# Control.net
KiCad netlist of a schematic drawn in Altium Designer
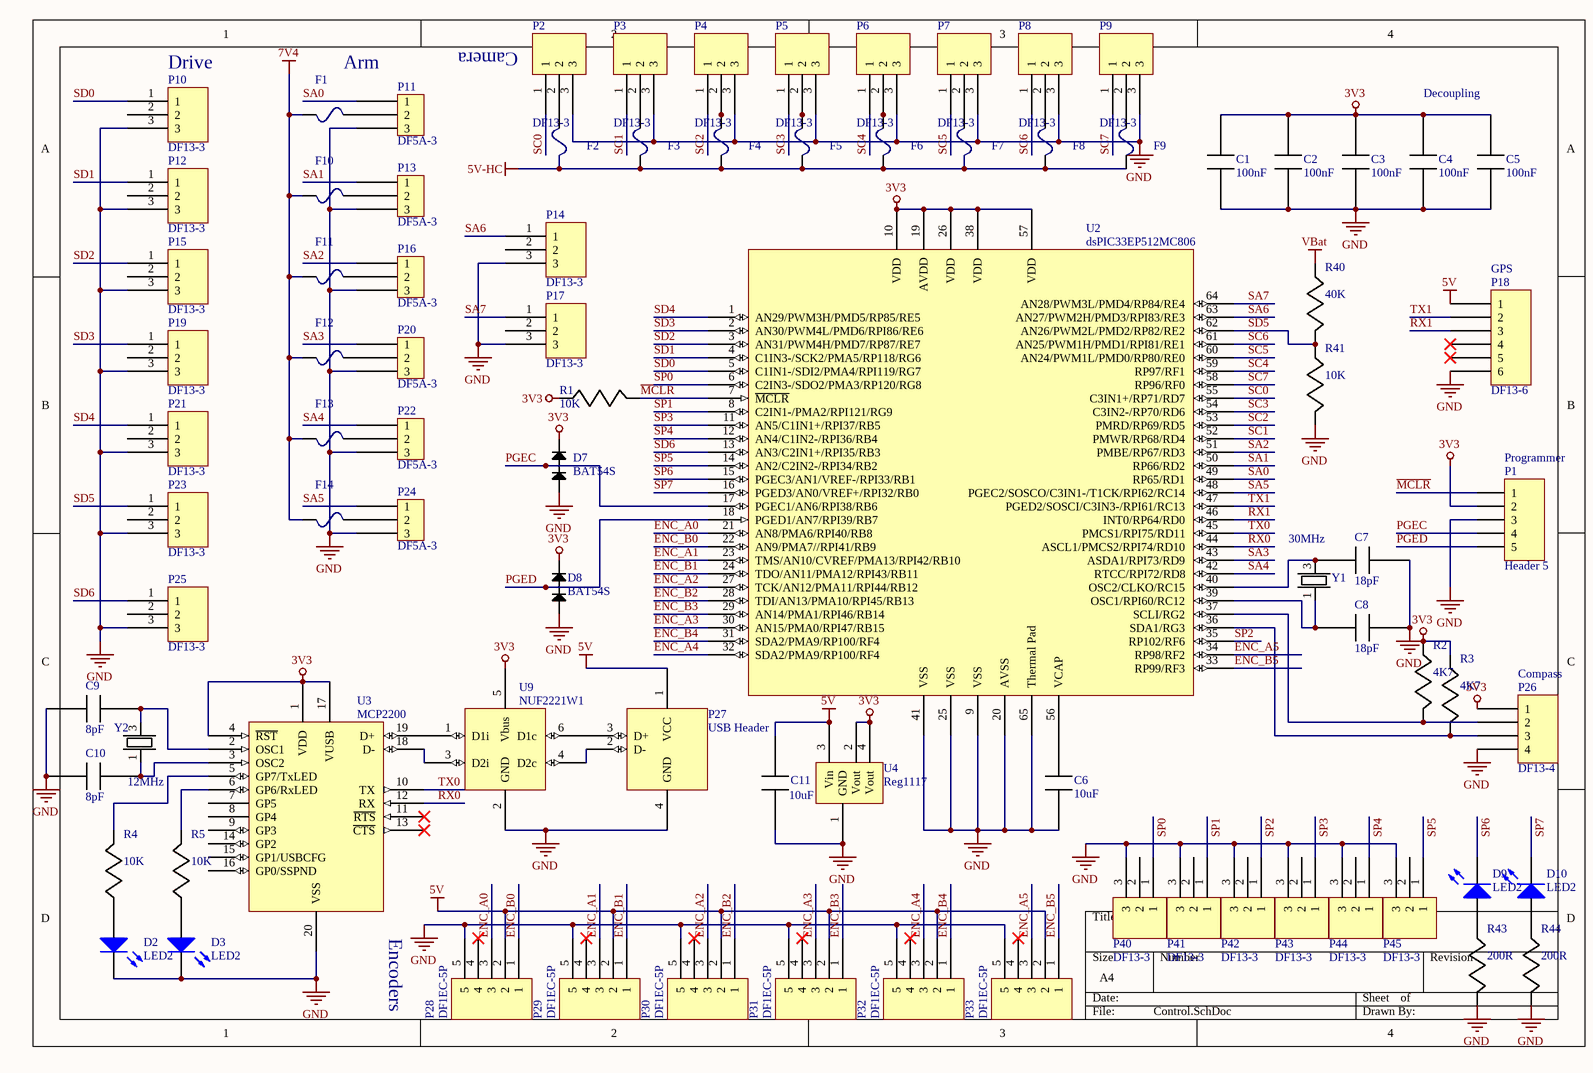
[diagram p0: Control.SchDoc]

(export (version "E")
  (design (tool "Eeschema 10.0.6"))
  (components
    (comp (ref "C1")
      (value "100nF")
      (footprint "1608[0603]")
      (libsource (lib "ControlBoard") (part "Capacitor"))
    )
    (comp (ref "C2")
      (value "100nF")
      (footprint "1608[0603]")
      (libsource (lib "ControlBoard") (part "Capacitor"))
    )
    (comp (ref "C3")
      (value "100nF")
      (footprint "1608[0603]")
      (libsource (lib "ControlBoard") (part "Capacitor"))
    )
    (comp (ref "C4")
      (value "100nF")
      (footprint "1608[0603]")
      (libsource (lib "ControlBoard") (part "Capacitor"))
    )
    (comp (ref "C5")
      (value "100nF")
      (footprint "1608[0603]")
      (libsource (lib "ControlBoard") (part "Capacitor"))
    )
    (comp (ref "C6")
      (value "10uF")
      (footprint "1608[0603]")
      (libsource (lib "ControlBoard") (part "Capacitor"))
    )
    (comp (ref "C7")
      (value "18pF")
      (footprint "1608[0603]")
      (libsource (lib "ControlBoard") (part "Capacitor"))
    )
    (comp (ref "C8")
      (value "18pF")
      (footprint "1608[0603]")
      (libsource (lib "ControlBoard") (part "Capacitor"))
    )
    (comp (ref "C9")
      (value "8pF")
      (footprint "1608[0603]")
      (libsource (lib "ControlBoard") (part "Capacitor"))
    )
    (comp (ref "C10")
      (value "8pF")
      (footprint "1608[0603]")
      (libsource (lib "ControlBoard") (part "Capacitor"))
    )
    (comp (ref "C11")
      (value "~")
      (footprint "1608[0603]")
      (fields (field (name "SIZE") "10uF"))
      (libsource (lib "ControlBoard") (part "Capacitor"))
    )
    (comp (ref "D2")
      (value "LED2")
      (footprint "3.2X1.6X1.1")
      (description "Typical RED, GREEN, YELLOW, AMBER GaAs LED")
      (fields (field (name "PUBLISHER") "Altium Limited"))
      (libsource (lib "Miscellaneous Devices") (part "LED2"))
    )
    (comp (ref "D3")
      (value "LED2")
      (footprint "3.2X1.6X1.1")
      (description "Typical RED, GREEN, YELLOW, AMBER GaAs LED")
      (fields (field (name "PUBLISHER") "Altium Limited"))
      (libsource (lib "Miscellaneous Devices") (part "LED2"))
    )
    (comp (ref "D7")
      (value "BAT54S")
      (footprint "SOT90P240X110-3N")
      (libsource (lib "ControlBoard") (part "BAT54S"))
    )
    (comp (ref "D8")
      (value "BAT54S")
      (footprint "SOT90P240X110-3N")
      (libsource (lib "ControlBoard") (part "BAT54S"))
    )
    (comp (ref "D9")
      (value "LED2")
      (footprint "1608[0603]")
      (description "Typical RED, GREEN, YELLOW, AMBER GaAs LED")
      (fields (field (name "PUBLISHER") "Altium Limited"))
      (libsource (lib "Miscellaneous Devices") (part "LED2"))
    )
    (comp (ref "D10")
      (value "LED2")
      (footprint "1608[0603]")
      (description "Typical RED, GREEN, YELLOW, AMBER GaAs LED")
      (fields (field (name "PUBLISHER") "Altium Limited"))
      (libsource (lib "Miscellaneous Devices") (part "LED2"))
    )
    (comp (ref "F1")
      (value "RSTA 2-BULK")
      (footprint "56400001009")
      (description "FUSE 2A 250/277V RADIAL")
      (libsource (lib "ControlBoard") (part "RSTA 2-BULK"))
    )
    (comp (ref "F2")
      (value "RSTA 2-BULK")
      (footprint "56400001009")
      (description "FUSE 2A 250/277V RADIAL")
      (libsource (lib "ControlBoard") (part "RSTA 2-BULK"))
    )
    (comp (ref "F3")
      (value "RSTA 2-BULK")
      (footprint "56400001009")
      (description "FUSE 2A 250/277V RADIAL")
      (libsource (lib "ControlBoard") (part "RSTA 2-BULK"))
    )
    (comp (ref "F4")
      (value "RSTA 2-BULK")
      (footprint "56400001009")
      (description "FUSE 2A 250/277V RADIAL")
      (libsource (lib "ControlBoard") (part "RSTA 2-BULK"))
    )
    (comp (ref "F5")
      (value "RSTA 2-BULK")
      (footprint "56400001009")
      (description "FUSE 2A 250/277V RADIAL")
      (libsource (lib "ControlBoard") (part "RSTA 2-BULK"))
    )
    (comp (ref "F6")
      (value "RSTA 2-BULK")
      (footprint "56400001009")
      (description "FUSE 2A 250/277V RADIAL")
      (libsource (lib "ControlBoard") (part "RSTA 2-BULK"))
    )
    (comp (ref "F7")
      (value "RSTA 2-BULK")
      (footprint "56400001009")
      (description "FUSE 2A 250/277V RADIAL")
      (libsource (lib "ControlBoard") (part "RSTA 2-BULK"))
    )
    (comp (ref "F8")
      (value "RSTA 2-BULK")
      (footprint "56400001009")
      (description "FUSE 2A 250/277V RADIAL")
      (libsource (lib "ControlBoard") (part "RSTA 2-BULK"))
    )
    (comp (ref "F9")
      (value "RSTA 2-BULK")
      (footprint "56400001009")
      (description "FUSE 2A 250/277V RADIAL")
      (libsource (lib "ControlBoard") (part "RSTA 2-BULK"))
    )
    (comp (ref "F10")
      (value "RSTA 2-BULK")
      (footprint "56400001009")
      (description "FUSE 2A 250/277V RADIAL")
      (libsource (lib "ControlBoard") (part "RSTA 2-BULK"))
    )
    (comp (ref "F11")
      (value "RSTA 2-BULK")
      (footprint "56400001009")
      (description "FUSE 2A 250/277V RADIAL")
      (libsource (lib "ControlBoard") (part "RSTA 2-BULK"))
    )
    (comp (ref "F12")
      (value "RSTA 2-BULK")
      (footprint "56400001009")
      (description "FUSE 2A 250/277V RADIAL")
      (libsource (lib "ControlBoard") (part "RSTA 2-BULK"))
    )
    (comp (ref "F13")
      (value "RSTA 2-BULK")
      (footprint "56400001009")
      (description "FUSE 2A 250/277V RADIAL")
      (libsource (lib "ControlBoard") (part "RSTA 2-BULK"))
    )
    (comp (ref "F14")
      (value "RSTA 2-BULK")
      (footprint "56400001009")
      (description "FUSE 2A 250/277V RADIAL")
      (libsource (lib "ControlBoard") (part "RSTA 2-BULK"))
    )
    (comp (ref "P1")
      (value "Header 5")
      (footprint "HDR1X5")
      (description "Header, 5-Pin")
      (fields (field (name "PUBLISHER") "Altium Limited"))
      (libsource (lib "Miscellaneous Connectors") (part "Header 5"))
    )
    (comp (ref "P2") (value "DF13-3") (footprint "DF13-3") (libsource (lib "") (part "DF13-3_1")))
    (comp (ref "P3") (value "DF13-3") (footprint "DF13-3") (libsource (lib "") (part "DF13-3_1")))
    (comp (ref "P4") (value "DF13-3") (footprint "DF13-3") (libsource (lib "") (part "DF13-3_1")))
    (comp (ref "P5") (value "DF13-3") (footprint "DF13-3") (libsource (lib "") (part "DF13-3_1")))
    (comp (ref "P6") (value "DF13-3") (footprint "DF13-3") (libsource (lib "") (part "DF13-3_1")))
    (comp (ref "P7") (value "DF13-3") (footprint "DF13-3") (libsource (lib "") (part "DF13-3_1")))
    (comp (ref "P8") (value "DF13-3") (footprint "DF13-3") (libsource (lib "") (part "DF13-3_1")))
    (comp (ref "P9") (value "DF13-3") (footprint "DF13-3") (libsource (lib "") (part "DF13-3_1")))
    (comp (ref "P10") (value "DF13-3") (footprint "DF13-3") (libsource (lib "") (part "DF13-3_2")))
    (comp (ref "P11") (value "DF5A-3") (footprint "DF5A-3") (libsource (lib "ControlBoard") (part "DF5A-3")))
    (comp (ref "P12") (value "DF13-3") (footprint "DF13-3") (libsource (lib "") (part "DF13-3_2")))
    (comp (ref "P13") (value "DF5A-3") (footprint "DF5A-3") (libsource (lib "ControlBoard") (part "DF5A-3")))
    (comp (ref "P14") (value "DF13-3") (footprint "DF13-3") (libsource (lib "") (part "DF13-3_2")))
    (comp (ref "P15") (value "DF13-3") (footprint "DF13-3") (libsource (lib "") (part "DF13-3_2")))
    (comp (ref "P16") (value "DF5A-3") (footprint "DF5A-3") (libsource (lib "ControlBoard") (part "DF5A-3")))
    (comp (ref "P17") (value "DF13-3") (footprint "DF13-3") (libsource (lib "") (part "DF13-3_2")))
    (comp (ref "P18")
      (value "DF13-6")
      (footprint "DF13-6S-1.25H")
      (libsource (lib "ControlBoard") (part "DF13-6"))
    )
    (comp (ref "P19") (value "DF13-3") (footprint "DF13-3") (libsource (lib "") (part "DF13-3_2")))
    (comp (ref "P20") (value "DF5A-3") (footprint "DF5A-3") (libsource (lib "ControlBoard") (part "DF5A-3")))
    (comp (ref "P21") (value "DF13-3") (footprint "DF13-3") (libsource (lib "") (part "DF13-3_2")))
    (comp (ref "P22") (value "DF5A-3") (footprint "DF5A-3") (libsource (lib "ControlBoard") (part "DF5A-3")))
    (comp (ref "P23") (value "DF13-3") (footprint "DF13-3") (libsource (lib "") (part "DF13-3_2")))
    (comp (ref "P24") (value "DF5A-3") (footprint "DF5A-3") (libsource (lib "ControlBoard") (part "DF5A-3")))
    (comp (ref "P25") (value "DF13-3") (footprint "DF13-3") (libsource (lib "") (part "DF13-3_2")))
    (comp (ref "P26")
      (value "DF13-4")
      (footprint "DF13-4S-1.25H")
      (libsource (lib "ControlBoard") (part "DF13-4"))
    )
    (comp (ref "P27")
      (value "USB Header")
      (footprint "USB-B")
      (libsource (lib "ControlBoard") (part "USB Header"))
    )
    (comp (ref "P28")
      (value "DF1EC-5P")
      (footprint "DF1EC-4P")
      (libsource (lib "ControlBoard") (part "DF1EC-5P"))
    )
    (comp (ref "P29")
      (value "DF1EC-5P")
      (footprint "DF1EC-4P")
      (libsource (lib "ControlBoard") (part "DF1EC-5P"))
    )
    (comp (ref "P30")
      (value "DF1EC-5P")
      (footprint "DF1EC-4P")
      (libsource (lib "ControlBoard") (part "DF1EC-5P"))
    )
    (comp (ref "P31")
      (value "DF1EC-5P")
      (footprint "DF1EC-4P")
      (libsource (lib "ControlBoard") (part "DF1EC-5P"))
    )
    (comp (ref "P32")
      (value "DF1EC-5P")
      (footprint "DF1EC-4P")
      (libsource (lib "ControlBoard") (part "DF1EC-5P"))
    )
    (comp (ref "P33")
      (value "DF1EC-5P")
      (footprint "DF1EC-4P")
      (libsource (lib "ControlBoard") (part "DF1EC-5P"))
    )
    (comp (ref "P40") (value "DF13-3") (footprint "DF13-3") (libsource (lib "ControlBoard") (part "DF13-3")))
    (comp (ref "P41") (value "DF13-3") (footprint "DF13-3") (libsource (lib "ControlBoard") (part "DF13-3")))
    (comp (ref "P42") (value "DF13-3") (footprint "DF13-3") (libsource (lib "ControlBoard") (part "DF13-3")))
    (comp (ref "P43") (value "DF13-3") (footprint "DF13-3") (libsource (lib "ControlBoard") (part "DF13-3")))
    (comp (ref "P44") (value "DF13-3") (footprint "DF13-3") (libsource (lib "ControlBoard") (part "DF13-3")))
    (comp (ref "P45") (value "DF13-3") (footprint "DF13-3") (libsource (lib "ControlBoard") (part "DF13-3")))
    (comp (ref "R1")
      (value "~")
      (footprint "1608[0603]")
      (fields (field (name "SIZE") "10K"))
      (libsource (lib "ControlBoard") (part "Resistor"))
    )
    (comp (ref "R2")
      (value "~")
      (footprint "1608[0603]")
      (fields (field (name "SIZE") "4K7"))
      (libsource (lib "ControlBoard") (part "Resistor"))
    )
    (comp (ref "R3")
      (value "~")
      (footprint "1608[0603]")
      (fields (field (name "SIZE") "4K7"))
      (libsource (lib "ControlBoard") (part "Resistor"))
    )
    (comp (ref "R4")
      (value "~")
      (footprint "1608[0603]")
      (fields (field (name "SIZE") "10K"))
      (libsource (lib "ControlBoard") (part "Resistor"))
    )
    (comp (ref "R5")
      (value "~")
      (footprint "1608[0603]")
      (fields (field (name "SIZE") "10K"))
      (libsource (lib "ControlBoard") (part "Resistor"))
    )
    (comp (ref "R40")
      (value "~")
      (footprint "1608[0603]")
      (fields (field (name "SIZE") "40K"))
      (libsource (lib "ControlBoard") (part "Resistor"))
    )
    (comp (ref "R41")
      (value "~")
      (footprint "1608[0603]")
      (fields (field (name "SIZE") "10K"))
      (libsource (lib "ControlBoard") (part "Resistor"))
    )
    (comp (ref "R43")
      (value "~")
      (footprint "1608[0603]")
      (fields (field (name "SIZE") "200R"))
      (libsource (lib "ControlBoard") (part "Resistor"))
    )
    (comp (ref "R44")
      (value "~")
      (footprint "1608[0603]")
      (fields (field (name "SIZE") "200R"))
      (libsource (lib "ControlBoard") (part "Resistor"))
    )
    (comp (ref "U2")
      (value "dsPIC33EP512MC806")
      (footprint "QFN50P900X900X100_HS-65N")
      (libsource (lib "ControlBoard") (part "dsPIC33EP512MC806"))
    )
    (comp (ref "U3")
      (value "MCP2200")
      (footprint "SOP65P780X200-20N")
      (libsource (lib "ControlBoard") (part "MCP2200"))
    )
    (comp (ref "U4")
      (value "Reg1117")
      (footprint "SOT230P700X180-4N")
      (libsource (lib "ControlBoard") (part "Reg1117"))
    )
    (comp (ref "U9")
      (value "NUF2221W1")
      (footprint "TSOP65P210X110-6N")
      (libsource (lib "ControlBoard") (part "NUF2221W1"))
    )
    (comp (ref "Y1")
      (value "30MHz")
      (footprint "7M-30.000MBBK-T")
      (fields (field (name "Comment") "NX5032GC"))
      (libsource (lib "ControlBoard") (part "NX5032GC"))
    )
    (comp (ref "Y2")
      (value "12MHz")
      (footprint "NX5032GC")
      (fields (field (name "Comment") "NX5032GC"))
      (libsource (lib "ControlBoard") (part "NX5032GC"))
    )
  )
  (nets
    (net (code "1") (name "/ENC_A0") (class "Default")
      (node (ref "P28") (pin "3") (pinfunction "3_3") (pintype "passive"))
      (node (ref "U2") (pin "21") (pinfunction "AN8/PMA6/RPI40/RB8_21") (pintype "bidirectional"))
    )
    (net (code "2") (name "/ENC_A1") (class "Default")
      (node (ref "P29") (pin "3") (pinfunction "3_3") (pintype "passive"))
      (node (ref "U2") (pin "23") (pinfunction "TMS/AN10/CVREF/PMA13/RPI42/RB10_23") (pintype "bidirectional"))
    )
    (net (code "3") (name "/ENC_A2") (class "Default")
      (node (ref "P30") (pin "3") (pinfunction "3_3") (pintype "passive"))
      (node (ref "U2") (pin "27") (pinfunction "TCK/AN12/PMA11/RPI44/RB12_27") (pintype "bidirectional"))
    )
    (net (code "4") (name "/ENC_A3") (class "Default")
      (node (ref "P31") (pin "3") (pinfunction "3_3") (pintype "passive"))
      (node (ref "U2") (pin "30") (pinfunction "AN15/PMA0/RPI47/RB15_30") (pintype "bidirectional"))
    )
    (net (code "5") (name "/ENC_A4") (class "Default")
      (node (ref "P32") (pin "3") (pinfunction "3_3") (pintype "passive"))
      (node (ref "U2") (pin "32") (pinfunction "SDA2/PMA9/RP100/RF4_32") (pintype "bidirectional"))
    )
    (net (code "6") (name "/ENC_A5") (class "Default")
      (node (ref "P33") (pin "3") (pinfunction "3_3") (pintype "passive"))
      (node (ref "U2") (pin "34") (pinfunction "RP98/RF2_34") (pintype "bidirectional"))
    )
    (net (code "7") (name "/ENC_B0") (class "Default")
      (node (ref "P28") (pin "1") (pinfunction "1_1") (pintype "passive"))
      (node (ref "U2") (pin "22") (pinfunction "AN9/PMA7//RPI41/RB9_22") (pintype "bidirectional"))
    )
    (net (code "8") (name "/ENC_B1") (class "Default")
      (node (ref "P29") (pin "1") (pinfunction "1_1") (pintype "passive"))
      (node (ref "U2") (pin "24") (pinfunction "TDO/AN11/PMA12/RPI43/RB11_24") (pintype "bidirectional"))
    )
    (net (code "9") (name "/ENC_B2") (class "Default")
      (node (ref "P30") (pin "1") (pinfunction "1_1") (pintype "passive"))
      (node (ref "U2") (pin "28") (pinfunction "TDI/AN13/PMA10/RPI45/RB13_28") (pintype "bidirectional"))
    )
    (net (code "10") (name "/ENC_B3") (class "Default")
      (node (ref "P31") (pin "1") (pinfunction "1_1") (pintype "passive"))
      (node (ref "U2") (pin "29") (pinfunction "AN14/PMA1/RPI46/RB14_29") (pintype "bidirectional"))
    )
    (net (code "11") (name "/ENC_B4") (class "Default")
      (node (ref "P32") (pin "1") (pinfunction "1_1") (pintype "passive"))
      (node (ref "U2") (pin "31") (pinfunction "SDA2/PMA9/RP100/RF4_31") (pintype "bidirectional"))
    )
    (net (code "12") (name "/ENC_B5") (class "Default")
      (node (ref "P33") (pin "1") (pinfunction "1_1") (pintype "passive"))
      (node (ref "U2") (pin "33") (pinfunction "RP99/RF3_33") (pintype "bidirectional"))
    )
    (net (code "13") (name "/PGEC") (class "Default")
      (node (ref "D7") (pin "3") (pinfunction "D1i_3") (pintype "passive"))
      (node (ref "P1") (pin "4") (pinfunction "4_4") (pintype "passive"))
      (node (ref "U2") (pin "17") (pinfunction "PGEC1/AN6/RPI38/RB6_17") (pintype "bidirectional"))
    )
    (net (code "14") (name "/PGED") (class "Default")
      (node (ref "D8") (pin "3") (pinfunction "D1i_3") (pintype "passive"))
      (node (ref "P1") (pin "5") (pinfunction "5_5") (pintype "passive"))
      (node (ref "U2") (pin "18") (pinfunction "PGED1/AN7/RPI39/RB7_18") (pintype "input"))
    )
    (net (code "15") (name "/RX0") (class "Default")
      (node (ref "U2") (pin "44") (pinfunction "ASCL1/PMCS2/RPI74/RD10_44") (pintype "bidirectional"))
      (node (ref "U3") (pin "12") (pinfunction "RX_12") (pintype "input"))
    )
    (net (code "16") (name "/RX1") (class "Default")
      (node (ref "P18") (pin "3") (pinfunction "3_3") (pintype "passive"))
      (node (ref "U2") (pin "46") (pinfunction "INT0/RP64/RD0_46") (pintype "bidirectional"))
    )
    (net (code "17") (name "/SA0") (class "Default")
      (node (ref "P11") (pin "1") (pinfunction "1_1") (pintype "passive"))
      (node (ref "U2") (pin "49") (pinfunction "RP65/RD1_49") (pintype "bidirectional"))
    )
    (net (code "18") (name "/SA1") (class "Default")
      (node (ref "P13") (pin "1") (pinfunction "1_1") (pintype "passive"))
      (node (ref "U2") (pin "50") (pinfunction "RP66/RD2_50") (pintype "bidirectional"))
    )
    (net (code "19") (name "/SA2") (class "Default")
      (node (ref "P16") (pin "1") (pinfunction "1_1") (pintype "passive"))
      (node (ref "U2") (pin "51") (pinfunction "PMBE/RP67/RD3_51") (pintype "bidirectional"))
    )
    (net (code "20") (name "/SA3") (class "Default")
      (node (ref "P20") (pin "1") (pinfunction "1_1") (pintype "passive"))
      (node (ref "U2") (pin "43") (pinfunction "ASDA1/RPI73/RD9_43") (pintype "bidirectional"))
    )
    (net (code "21") (name "/SA4") (class "Default")
      (node (ref "P22") (pin "1") (pinfunction "1_1") (pintype "passive"))
      (node (ref "U2") (pin "42") (pinfunction "RTCC/RPI72/RD8_42") (pintype "bidirectional"))
    )
    (net (code "22") (name "/SA5") (class "Default")
      (node (ref "P24") (pin "1") (pinfunction "1_1") (pintype "passive"))
      (node (ref "U2") (pin "48") (pinfunction "PGEC2/SOSCO/C3IN1-/T1CK/RPI62/RC14_48") (pintype "bidirectional"))
    )
    (net (code "23") (name "/SA6") (class "Default")
      (node (ref "P14") (pin "1") (pinfunction "1_1") (pintype "passive"))
      (node (ref "U2") (pin "63") (pinfunction "AN27/PWM2H/PMD3/RPI83/RE3_63") (pintype "bidirectional"))
    )
    (net (code "24") (name "/SA7") (class "Default")
      (node (ref "P17") (pin "1") (pinfunction "1_1") (pintype "passive"))
      (node (ref "U2") (pin "64") (pinfunction "AN28/PWM3L/PMD4/RP84/RE4_64") (pintype "bidirectional"))
    )
    (net (code "25") (name "/SC0") (class "Default")
      (node (ref "P2") (pin "1") (pinfunction "1_1") (pintype "passive"))
      (node (ref "U2") (pin "55") (pinfunction "C3IN1+/RP71/RD7_55") (pintype "bidirectional"))
    )
    (net (code "26") (name "/SC1") (class "Default")
      (node (ref "P3") (pin "1") (pinfunction "1_1") (pintype "passive"))
      (node (ref "U2") (pin "52") (pinfunction "PMWR/RP68/RD4_52") (pintype "bidirectional"))
    )
    (net (code "27") (name "/SC2") (class "Default")
      (node (ref "P4") (pin "1") (pinfunction "1_1") (pintype "passive"))
      (node (ref "U2") (pin "53") (pinfunction "PMRD/RP69/RD5_53") (pintype "bidirectional"))
    )
    (net (code "28") (name "/SC3") (class "Default")
      (node (ref "P5") (pin "1") (pinfunction "1_1") (pintype "passive"))
      (node (ref "U2") (pin "54") (pinfunction "C3IN2-/RP70/RD6_54") (pintype "bidirectional"))
    )
    (net (code "29") (name "/SC4") (class "Default")
      (node (ref "P6") (pin "1") (pinfunction "1_1") (pintype "passive"))
      (node (ref "U2") (pin "59") (pinfunction "RP97/RF1_59") (pintype "bidirectional"))
    )
    (net (code "30") (name "/SC5") (class "Default")
      (node (ref "P7") (pin "1") (pinfunction "1_1") (pintype "passive"))
      (node (ref "U2") (pin "60") (pinfunction "AN24/PWM1L/PMD0/RP80/RE0_60") (pintype "bidirectional"))
    )
    (net (code "31") (name "/SC6") (class "Default")
      (node (ref "P8") (pin "1") (pinfunction "1_1") (pintype "passive"))
      (node (ref "U2") (pin "61") (pinfunction "AN25/PWM1H/PMD1/RPI81/RE1_61") (pintype "bidirectional"))
    )
    (net (code "32") (name "/SC7") (class "Default")
      (node (ref "P9") (pin "1") (pinfunction "1_1") (pintype "passive"))
      (node (ref "U2") (pin "58") (pinfunction "RP96/RF0_58") (pintype "bidirectional"))
    )
    (net (code "33") (name "/SD0") (class "Default")
      (node (ref "P10") (pin "1") (pinfunction "1_1") (pintype "passive"))
      (node (ref "U2") (pin "5") (pinfunction "C1IN1-/SDI2/PMA4/RPI119/RG7_5") (pintype "bidirectional"))
    )
    (net (code "34") (name "/SD1") (class "Default")
      (node (ref "P12") (pin "1") (pinfunction "1_1") (pintype "passive"))
      (node (ref "U2") (pin "4") (pinfunction "C1IN3-/SCK2/PMA5/RP118/RG6_4") (pintype "bidirectional"))
    )
    (net (code "35") (name "/SD2") (class "Default")
      (node (ref "P15") (pin "1") (pinfunction "1_1") (pintype "passive"))
      (node (ref "U2") (pin "3") (pinfunction "AN31/PWM4H/PMD7/RP87/RE7_3") (pintype "bidirectional"))
    )
    (net (code "36") (name "/SD3") (class "Default")
      (node (ref "P19") (pin "1") (pinfunction "1_1") (pintype "passive"))
      (node (ref "U2") (pin "2") (pinfunction "AN30/PWM4L/PMD6/RPI86/RE6_2") (pintype "bidirectional"))
    )
    (net (code "37") (name "/SD4") (class "Default")
      (node (ref "P21") (pin "1") (pinfunction "1_1") (pintype "passive"))
      (node (ref "U2") (pin "1") (pinfunction "AN29/PWM3H/PMD5/RP85/RE5_1") (pintype "bidirectional"))
    )
    (net (code "38") (name "/SD5") (class "Default")
      (node (ref "P23") (pin "1") (pinfunction "1_1") (pintype "passive"))
      (node (ref "R40") (pin "1") (pinfunction "1_1") (pintype "passive"))
      (node (ref "R41") (pin "2") (pinfunction "2_2") (pintype "passive"))
      (node (ref "U2") (pin "62") (pinfunction "AN26/PWM2L/PMD2/RP82/RE2_62") (pintype "bidirectional"))
    )
    (net (code "39") (name "/SD6") (class "Default")
      (node (ref "P25") (pin "1") (pinfunction "1_1") (pintype "passive"))
      (node (ref "U2") (pin "13") (pinfunction "AN3/C2IN1+/RPI35/RB3_13") (pintype "bidirectional"))
    )
    (net (code "40") (name "/SP0") (class "Default")
      (node (ref "P40") (pin "1") (pinfunction "1_1") (pintype "passive"))
      (node (ref "U2") (pin "6") (pinfunction "C2IN3-/SDO2/PMA3/RP120/RG8_6") (pintype "bidirectional"))
    )
    (net (code "41") (name "/SP1") (class "Default")
      (node (ref "P41") (pin "1") (pinfunction "1_1") (pintype "passive"))
      (node (ref "U2") (pin "8") (pinfunction "C2IN1-/PMA2/RPI121/RG9_8") (pintype "bidirectional"))
    )
    (net (code "42") (name "/SP2") (class "Default")
      (node (ref "P42") (pin "1") (pinfunction "1_1") (pintype "passive"))
      (node (ref "U2") (pin "35") (pinfunction "RP102/RF6_35") (pintype "bidirectional"))
    )
    (net (code "43") (name "/SP3") (class "Default")
      (node (ref "P43") (pin "1") (pinfunction "1_1") (pintype "passive"))
      (node (ref "U2") (pin "11") (pinfunction "AN5/C1IN1+/RPI37/RB5_11") (pintype "bidirectional"))
    )
    (net (code "44") (name "/SP4") (class "Default")
      (node (ref "P44") (pin "1") (pinfunction "1_1") (pintype "passive"))
      (node (ref "U2") (pin "12") (pinfunction "AN4/C1IN2-/RPI36/RB4_12") (pintype "bidirectional"))
    )
    (net (code "45") (name "/SP5") (class "Default")
      (node (ref "P45") (pin "1") (pinfunction "1_1") (pintype "passive"))
      (node (ref "U2") (pin "14") (pinfunction "AN2/C2IN2-/RPI34/RB2_14") (pintype "bidirectional"))
    )
    (net (code "46") (name "/SP6") (class "Default")
      (node (ref "D9") (pin "2") (pinfunction "K_2") (pintype "passive"))
      (node (ref "U2") (pin "15") (pinfunction "PGEC3/AN1/VREF-/RPI33/RB1_15") (pintype "bidirectional"))
    )
    (net (code "47") (name "/SP7") (class "Default")
      (node (ref "D10") (pin "2") (pinfunction "K_2") (pintype "passive"))
      (node (ref "U2") (pin "16") (pinfunction "PGED3/AN0/VREF+/RPI32/RB0_16") (pintype "bidirectional"))
    )
    (net (code "48") (name "/TX0") (class "Default")
      (node (ref "U2") (pin "45") (pinfunction "PMCS1/RPI75/RD11_45") (pintype "bidirectional"))
      (node (ref "U3") (pin "10") (pinfunction "TX_10") (pintype "output"))
    )
    (net (code "49") (name "/TX1") (class "Default")
      (node (ref "P18") (pin "2") (pinfunction "2_2") (pintype "passive"))
      (node (ref "U2") (pin "47") (pinfunction "PGED2/SOSCI/C3IN3-/RPI61/RC13_47") (pintype "bidirectional"))
    )
    (net (code "50") (name "/~{MCLR}") (class "Default")
      (node (ref "P1") (pin "1") (pinfunction "1_1") (pintype "passive"))
      (node (ref "R1") (pin "1") (pinfunction "1_1") (pintype "passive"))
      (node (ref "U2") (pin "7") (pinfunction "~{MCLR}_7") (pintype "input"))
    )
    (net (code "51") (name "3V3") (class "Default")
      (node (ref "C1") (pin "2") (pinfunction "2_2") (pintype "passive"))
      (node (ref "C2") (pin "2") (pinfunction "2_2") (pintype "passive"))
      (node (ref "C3") (pin "2") (pinfunction "2_2") (pintype "passive"))
      (node (ref "C4") (pin "2") (pinfunction "2_2") (pintype "passive"))
      (node (ref "C5") (pin "2") (pinfunction "2_2") (pintype "passive"))
      (node (ref "D7") (pin "2") (pinfunction "D1i_2") (pintype "passive"))
      (node (ref "D8") (pin "2") (pinfunction "D1i_2") (pintype "passive"))
      (node (ref "P1") (pin "2") (pinfunction "2_2") (pintype "passive"))
      (node (ref "P26") (pin "1") (pinfunction "1_1") (pintype "passive"))
      (node (ref "R1") (pin "2") (pinfunction "2_2") (pintype "passive"))
      (node (ref "R2") (pin "2") (pinfunction "2_2") (pintype "passive"))
      (node (ref "R3") (pin "2") (pinfunction "2_2") (pintype "passive"))
      (node (ref "U2") (pin "10") (pinfunction "VDD_10") (pintype "power_in"))
      (node (ref "U2") (pin "19") (pinfunction "AVDD_19") (pintype "power_in"))
      (node (ref "U2") (pin "26") (pinfunction "VDD_26") (pintype "passive"))
      (node (ref "U2") (pin "38") (pinfunction "VDD_38") (pintype "power_in"))
      (node (ref "U2") (pin "57") (pinfunction "VDD_57") (pintype "power_in"))
      (node (ref "U3") (pin "1") (pinfunction "VDD_1") (pintype "passive"))
      (node (ref "U3") (pin "17") (pinfunction "VUSB_17") (pintype "power_in"))
      (node (ref "U3") (pin "4") (pinfunction "~{RST}_4") (pintype "input"))
      (node (ref "U4") (pin "2") (pinfunction "Vout_2") (pintype "power_in"))
      (node (ref "U4") (pin "4") (pinfunction "Vout_4") (pintype "power_in"))
      (node (ref "U9") (pin "5") (pinfunction "Vbus_5") (pintype "power_in"))
    )
    (net (code "52") (name "5V") (class "Default")
      (node (ref "C11") (pin "2") (pinfunction "2_2") (pintype "passive"))
      (node (ref "P18") (pin "1") (pinfunction "1_1") (pintype "passive"))
      (node (ref "P27") (pin "1") (pinfunction "VCC_1") (pintype "power_in"))
      (node (ref "P28") (pin "2") (pinfunction "2_2") (pintype "passive"))
      (node (ref "P29") (pin "2") (pinfunction "2_2") (pintype "passive"))
      (node (ref "P30") (pin "2") (pinfunction "2_2") (pintype "passive"))
      (node (ref "P31") (pin "2") (pinfunction "2_2") (pintype "passive"))
      (node (ref "P32") (pin "2") (pinfunction "2_2") (pintype "passive"))
      (node (ref "P33") (pin "2") (pinfunction "2_2") (pintype "passive"))
      (node (ref "U4") (pin "3") (pinfunction "Vin_3") (pintype "power_in"))
    )
    (net (code "53") (name "5V-HC") (class "Default")
      (node (ref "F2") (pin "2") (pinfunction "31_2") (pintype "passive"))
      (node (ref "F3") (pin "1") (pinfunction "30_1") (pintype "passive"))
      (node (ref "F4") (pin "1") (pinfunction "30_1") (pintype "passive"))
      (node (ref "F5") (pin "1") (pinfunction "30_1") (pintype "passive"))
      (node (ref "F6") (pin "1") (pinfunction "30_1") (pintype "passive"))
      (node (ref "F7") (pin "1") (pinfunction "30_1") (pintype "passive"))
      (node (ref "F8") (pin "1") (pinfunction "30_1") (pintype "passive"))
      (node (ref "F9") (pin "1") (pinfunction "30_1") (pintype "passive"))
    )
    (net (code "54") (name "7V4") (class "Default")
      (node (ref "F1") (pin "1") (pinfunction "30_1") (pintype "passive"))
      (node (ref "F10") (pin "1") (pinfunction "30_1") (pintype "passive"))
      (node (ref "F11") (pin "1") (pinfunction "30_1") (pintype "passive"))
      (node (ref "F12") (pin "1") (pinfunction "30_1") (pintype "passive"))
      (node (ref "F13") (pin "1") (pinfunction "30_1") (pintype "passive"))
      (node (ref "F14") (pin "1") (pinfunction "30_1") (pintype "passive"))
    )
    (net (code "55") (name "GND") (class "Default")
      (node (ref "C1") (pin "1") (pinfunction "1_1") (pintype "passive"))
      (node (ref "C10") (pin "2") (pinfunction "2_2") (pintype "passive"))
      (node (ref "C11") (pin "1") (pinfunction "1_1") (pintype "passive"))
      (node (ref "C2") (pin "1") (pinfunction "1_1") (pintype "passive"))
      (node (ref "C3") (pin "1") (pinfunction "1_1") (pintype "passive"))
      (node (ref "C4") (pin "1") (pinfunction "1_1") (pintype "passive"))
      (node (ref "C5") (pin "1") (pinfunction "1_1") (pintype "passive"))
      (node (ref "C6") (pin "1") (pinfunction "1_1") (pintype "passive"))
      (node (ref "C7") (pin "1") (pinfunction "1_1") (pintype "passive"))
      (node (ref "C8") (pin "1") (pinfunction "1_1") (pintype "passive"))
      (node (ref "C9") (pin "2") (pinfunction "2_2") (pintype "passive"))
      (node (ref "D2") (pin "2") (pinfunction "K_2") (pintype "passive"))
      (node (ref "D3") (pin "2") (pinfunction "K_2") (pintype "passive"))
      (node (ref "D7") (pin "1") (pinfunction "D1i_1") (pintype "passive"))
      (node (ref "D8") (pin "1") (pinfunction "D1i_1") (pintype "passive"))
      (node (ref "P1") (pin "3") (pinfunction "3_3") (pintype "passive"))
      (node (ref "P10") (pin "3") (pinfunction "3_3") (pintype "passive"))
      (node (ref "P11") (pin "3") (pinfunction "3_3") (pintype "passive"))
      (node (ref "P12") (pin "3") (pinfunction "3_3") (pintype "passive"))
      (node (ref "P13") (pin "3") (pinfunction "3_3") (pintype "passive"))
      (node (ref "P14") (pin "3") (pinfunction "3_3") (pintype "passive"))
      (node (ref "P15") (pin "3") (pinfunction "3_3") (pintype "passive"))
      (node (ref "P16") (pin "3") (pinfunction "3_3") (pintype "passive"))
      (node (ref "P17") (pin "3") (pinfunction "3_3") (pintype "passive"))
      (node (ref "P18") (pin "6") (pinfunction "6_6") (pintype "passive"))
      (node (ref "P19") (pin "3") (pinfunction "3_3") (pintype "passive"))
      (node (ref "P2") (pin "3") (pinfunction "3_3") (pintype "passive"))
      (node (ref "P20") (pin "3") (pinfunction "3_3") (pintype "passive"))
      (node (ref "P21") (pin "3") (pinfunction "3_3") (pintype "passive"))
      (node (ref "P22") (pin "3") (pinfunction "3_3") (pintype "passive"))
      (node (ref "P23") (pin "3") (pinfunction "3_3") (pintype "passive"))
      (node (ref "P24") (pin "3") (pinfunction "3_3") (pintype "passive"))
      (node (ref "P25") (pin "3") (pinfunction "3_3") (pintype "passive"))
      (node (ref "P26") (pin "4") (pinfunction "4_4") (pintype "passive"))
      (node (ref "P27") (pin "4") (pinfunction "GND_4") (pintype "power_in"))
      (node (ref "P28") (pin "5") (pinfunction "5_5") (pintype "passive"))
      (node (ref "P29") (pin "5") (pinfunction "5_5") (pintype "passive"))
      (node (ref "P3") (pin "3") (pinfunction "3_3") (pintype "passive"))
      (node (ref "P30") (pin "5") (pinfunction "5_5") (pintype "passive"))
      (node (ref "P31") (pin "5") (pinfunction "5_5") (pintype "passive"))
      (node (ref "P32") (pin "5") (pinfunction "5_5") (pintype "passive"))
      (node (ref "P33") (pin "5") (pinfunction "5_5") (pintype "passive"))
      (node (ref "P4") (pin "3") (pinfunction "3_3") (pintype "passive"))
      (node (ref "P40") (pin "3") (pinfunction "3_3") (pintype "passive"))
      (node (ref "P41") (pin "3") (pinfunction "3_3") (pintype "passive"))
      (node (ref "P42") (pin "3") (pinfunction "3_3") (pintype "passive"))
      (node (ref "P43") (pin "3") (pinfunction "3_3") (pintype "passive"))
      (node (ref "P44") (pin "3") (pinfunction "3_3") (pintype "passive"))
      (node (ref "P45") (pin "3") (pinfunction "3_3") (pintype "passive"))
      (node (ref "P5") (pin "3") (pinfunction "3_3") (pintype "passive"))
      (node (ref "P6") (pin "3") (pinfunction "3_3") (pintype "passive"))
      (node (ref "P7") (pin "3") (pinfunction "3_3") (pintype "passive"))
      (node (ref "P8") (pin "3") (pinfunction "3_3") (pintype "passive"))
      (node (ref "P9") (pin "3") (pinfunction "3_3") (pintype "passive"))
      (node (ref "R41") (pin "1") (pinfunction "1_1") (pintype "passive"))
      (node (ref "R43") (pin "1") (pinfunction "1_1") (pintype "passive"))
      (node (ref "R44") (pin "1") (pinfunction "1_1") (pintype "passive"))
      (node (ref "U2") (pin "20") (pinfunction "AVSS_20") (pintype "passive"))
      (node (ref "U2") (pin "25") (pinfunction "VSS_25") (pintype "passive"))
      (node (ref "U2") (pin "41") (pinfunction "VSS_41") (pintype "power_in"))
      (node (ref "U2") (pin "65") (pinfunction "Thermal_Pad_65") (pintype "power_in"))
      (node (ref "U2") (pin "9") (pinfunction "VSS_9") (pintype "power_in"))
      (node (ref "U3") (pin "20") (pinfunction "VSS_20") (pintype "power_in"))
      (node (ref "U4") (pin "1") (pinfunction "GND_1") (pintype "power_in"))
      (node (ref "U9") (pin "2") (pinfunction "GND_2") (pintype "passive"))
    )
    (net (code "56") (name "Net-(D2-A)") (class "Default")
      (node (ref "D2") (pin "1") (pinfunction "A_1") (pintype "passive"))
      (node (ref "R4") (pin "2") (pinfunction "2_2") (pintype "passive"))
    )
    (net (code "57") (name "Net-(D3-A)") (class "Default")
      (node (ref "D3") (pin "1") (pinfunction "A_1") (pintype "passive"))
      (node (ref "R5") (pin "2") (pinfunction "2_2") (pintype "passive"))
    )
    (net (code "58") (name "Net-(D9-A)") (class "Default")
      (node (ref "D9") (pin "1") (pinfunction "A_1") (pintype "passive"))
      (node (ref "R43") (pin "2") (pinfunction "2_2") (pintype "passive"))
    )
    (net (code "59") (name "Net-(D10-A)") (class "Default")
      (node (ref "D10") (pin "1") (pinfunction "A_1") (pintype "passive"))
      (node (ref "R44") (pin "2") (pinfunction "2_2") (pintype "passive"))
    )
    (net (code "60") (name "Net-(F1-31)") (class "Default")
      (node (ref "F1") (pin "2") (pinfunction "31_2") (pintype "passive"))
      (node (ref "P11") (pin "2") (pinfunction "2_2") (pintype "passive"))
    )
    (net (code "61") (name "Net-(F2-30)") (class "Default")
      (node (ref "F2") (pin "1") (pinfunction "30_1") (pintype "passive"))
      (node (ref "P2") (pin "2") (pinfunction "2_2") (pintype "passive"))
    )
    (net (code "62") (name "Net-(F3-31)") (class "Default")
      (node (ref "F3") (pin "2") (pinfunction "31_2") (pintype "passive"))
      (node (ref "P3") (pin "2") (pinfunction "2_2") (pintype "passive"))
    )
    (net (code "63") (name "Net-(F4-31)") (class "Default")
      (node (ref "F4") (pin "2") (pinfunction "31_2") (pintype "passive"))
      (node (ref "P4") (pin "2") (pinfunction "2_2") (pintype "passive"))
    )
    (net (code "64") (name "Net-(F5-31)") (class "Default")
      (node (ref "F5") (pin "2") (pinfunction "31_2") (pintype "passive"))
      (node (ref "P5") (pin "2") (pinfunction "2_2") (pintype "passive"))
    )
    (net (code "65") (name "Net-(F6-31)") (class "Default")
      (node (ref "F6") (pin "2") (pinfunction "31_2") (pintype "passive"))
      (node (ref "P6") (pin "2") (pinfunction "2_2") (pintype "passive"))
    )
    (net (code "66") (name "Net-(F7-31)") (class "Default")
      (node (ref "F7") (pin "2") (pinfunction "31_2") (pintype "passive"))
      (node (ref "P7") (pin "2") (pinfunction "2_2") (pintype "passive"))
    )
    (net (code "67") (name "Net-(F8-31)") (class "Default")
      (node (ref "F8") (pin "2") (pinfunction "31_2") (pintype "passive"))
      (node (ref "P8") (pin "2") (pinfunction "2_2") (pintype "passive"))
    )
    (net (code "68") (name "Net-(F9-31)") (class "Default")
      (node (ref "F9") (pin "2") (pinfunction "31_2") (pintype "passive"))
      (node (ref "P9") (pin "2") (pinfunction "2_2") (pintype "passive"))
    )
    (net (code "69") (name "Net-(F10-31)") (class "Default")
      (node (ref "F10") (pin "2") (pinfunction "31_2") (pintype "passive"))
      (node (ref "P13") (pin "2") (pinfunction "2_2") (pintype "passive"))
    )
    (net (code "70") (name "Net-(F11-31)") (class "Default")
      (node (ref "F11") (pin "2") (pinfunction "31_2") (pintype "passive"))
      (node (ref "P16") (pin "2") (pinfunction "2_2") (pintype "passive"))
    )
    (net (code "71") (name "Net-(F12-31)") (class "Default")
      (node (ref "F12") (pin "2") (pinfunction "31_2") (pintype "passive"))
      (node (ref "P20") (pin "2") (pinfunction "2_2") (pintype "passive"))
    )
    (net (code "72") (name "Net-(F13-31)") (class "Default")
      (node (ref "F13") (pin "2") (pinfunction "31_2") (pintype "passive"))
      (node (ref "P22") (pin "2") (pinfunction "2_2") (pintype "passive"))
    )
    (net (code "73") (name "Net-(F14-31)") (class "Default")
      (node (ref "F14") (pin "2") (pinfunction "31_2") (pintype "passive"))
      (node (ref "P24") (pin "2") (pinfunction "2_2") (pintype "passive"))
    )
    (net (code "74") (name "Net-(P27-D+)") (class "Default")
      (node (ref "P27") (pin "3") (pinfunction "D+_3") (pintype "bidirectional"))
      (node (ref "U9") (pin "6") (pinfunction "D1c_6") (pintype "bidirectional"))
    )
    (net (code "75") (name "Net-(P27-D-)") (class "Default")
      (node (ref "P27") (pin "2") (pinfunction "D-_2") (pintype "bidirectional"))
      (node (ref "U9") (pin "4") (pinfunction "D2c_4") (pintype "bidirectional"))
    )
    (net (code "76") (name "Net-(U2-OSC1{slash}RPI60{slash}RC12)") (class "Default")
      (node (ref "C8") (pin "2") (pinfunction "2_2") (pintype "passive"))
      (node (ref "U2") (pin "39") (pinfunction "OSC1/RPI60/RC12_39") (pintype "bidirectional"))
      (node (ref "Y1") (pin "1") (pinfunction "1_1") (pintype "passive"))
    )
    (net (code "77") (name "Net-(U2-OSC2{slash}CLKO{slash}RC15)") (class "Default")
      (node (ref "C7") (pin "2") (pinfunction "2_2") (pintype "passive"))
      (node (ref "U2") (pin "40") (pinfunction "OSC2/CLKO/RC15_40") (pintype "bidirectional"))
      (node (ref "Y1") (pin "3") (pinfunction "3_3") (pintype "passive"))
    )
    (net (code "78") (name "Net-(U2-SCLI{slash}RG2)") (class "Default")
      (node (ref "P26") (pin "2") (pinfunction "2_2") (pintype "passive"))
      (node (ref "R2") (pin "1") (pinfunction "1_1") (pintype "passive"))
      (node (ref "U2") (pin "37") (pinfunction "SCLI/RG2_37") (pintype "bidirectional"))
    )
    (net (code "79") (name "Net-(U2-SDA1{slash}RG3)") (class "Default")
      (node (ref "P26") (pin "3") (pinfunction "3_3") (pintype "passive"))
      (node (ref "R3") (pin "1") (pinfunction "1_1") (pintype "passive"))
      (node (ref "U2") (pin "36") (pinfunction "SDA1/RG3_36") (pintype "bidirectional"))
    )
    (net (code "80") (name "Net-(U2-VCAP)") (class "Default")
      (node (ref "C6") (pin "2") (pinfunction "2_2") (pintype "passive"))
      (node (ref "U2") (pin "56") (pinfunction "VCAP_56") (pintype "power_in"))
    )
    (net (code "81") (name "Net-(U3-D+)") (class "Default")
      (node (ref "U3") (pin "19") (pinfunction "D+_19") (pintype "bidirectional"))
      (node (ref "U9") (pin "1") (pinfunction "D1i_1") (pintype "bidirectional"))
    )
    (net (code "82") (name "Net-(U3-D-)") (class "Default")
      (node (ref "U3") (pin "18") (pinfunction "D-_18") (pintype "bidirectional"))
      (node (ref "U9") (pin "3") (pinfunction "D2i_3") (pintype "bidirectional"))
    )
    (net (code "83") (name "Net-(U3-GP6{slash}RxLED)") (class "Default")
      (node (ref "R5") (pin "1") (pinfunction "1_1") (pintype "passive"))
      (node (ref "U3") (pin "6") (pinfunction "GP6/RxLED_6") (pintype "bidirectional"))
    )
    (net (code "84") (name "Net-(U3-GP7{slash}TxLED)") (class "Default")
      (node (ref "R4") (pin "1") (pinfunction "1_1") (pintype "passive"))
      (node (ref "U3") (pin "5") (pinfunction "GP7/TxLED_5") (pintype "bidirectional"))
    )
    (net (code "85") (name "Net-(U3-OSC1)") (class "Default")
      (node (ref "C9") (pin "1") (pinfunction "1_1") (pintype "passive"))
      (node (ref "U3") (pin "2") (pinfunction "OSC1_2") (pintype "input"))
      (node (ref "Y2") (pin "3") (pinfunction "3_3") (pintype "passive"))
    )
    (net (code "86") (name "Net-(U3-OSC2)") (class "Default")
      (node (ref "C10") (pin "1") (pinfunction "1_1") (pintype "passive"))
      (node (ref "U3") (pin "3") (pinfunction "OSC2_3") (pintype "input"))
      (node (ref "Y2") (pin "1") (pinfunction "1_1") (pintype "passive"))
    )
    (net (code "87") (name "VBat") (class "Default")
      (node (ref "R40") (pin "2") (pinfunction "2_2") (pintype "passive"))
    )
    (net (code "88") (name "unconnected-(P10-Pad2)") (class "Default")
      (node (ref "P10") (pin "2") (pinfunction "2_2") (pintype "passive"))
    )
    (net (code "89") (name "unconnected-(P12-Pad2)") (class "Default")
      (node (ref "P12") (pin "2") (pinfunction "2_2") (pintype "passive"))
    )
    (net (code "90") (name "unconnected-(P14-Pad2)") (class "Default")
      (node (ref "P14") (pin "2") (pinfunction "2_2") (pintype "passive"))
    )
    (net (code "91") (name "unconnected-(P15-Pad2)") (class "Default")
      (node (ref "P15") (pin "2") (pinfunction "2_2") (pintype "passive"))
    )
    (net (code "92") (name "unconnected-(P17-Pad2)") (class "Default")
      (node (ref "P17") (pin "2") (pinfunction "2_2") (pintype "passive"))
    )
    (net (code "93") (name "unconnected-(P18-Pad4)") (class "Default")
      (node (ref "P18") (pin "4") (pinfunction "4_4") (pintype "passive+no_connect"))
    )
    (net (code "94") (name "unconnected-(P18-Pad5)") (class "Default")
      (node (ref "P18") (pin "5") (pinfunction "5_5") (pintype "passive+no_connect"))
    )
    (net (code "95") (name "unconnected-(P19-Pad2)") (class "Default")
      (node (ref "P19") (pin "2") (pinfunction "2_2") (pintype "passive"))
    )
    (net (code "96") (name "unconnected-(P21-Pad2)") (class "Default")
      (node (ref "P21") (pin "2") (pinfunction "2_2") (pintype "passive"))
    )
    (net (code "97") (name "unconnected-(P23-Pad2)") (class "Default")
      (node (ref "P23") (pin "2") (pinfunction "2_2") (pintype "passive"))
    )
    (net (code "98") (name "unconnected-(P25-Pad2)") (class "Default")
      (node (ref "P25") (pin "2") (pinfunction "2_2") (pintype "passive"))
    )
    (net (code "99") (name "unconnected-(P28-Pad4)") (class "Default")
      (node (ref "P28") (pin "4") (pinfunction "4_4") (pintype "passive+no_connect"))
    )
    (net (code "100") (name "unconnected-(P29-Pad4)") (class "Default")
      (node (ref "P29") (pin "4") (pinfunction "4_4") (pintype "passive+no_connect"))
    )
    (net (code "101") (name "unconnected-(P30-Pad4)") (class "Default")
      (node (ref "P30") (pin "4") (pinfunction "4_4") (pintype "passive+no_connect"))
    )
    (net (code "102") (name "unconnected-(P31-Pad4)") (class "Default")
      (node (ref "P31") (pin "4") (pinfunction "4_4") (pintype "passive+no_connect"))
    )
    (net (code "103") (name "unconnected-(P32-Pad4)") (class "Default")
      (node (ref "P32") (pin "4") (pinfunction "4_4") (pintype "passive+no_connect"))
    )
    (net (code "104") (name "unconnected-(P33-Pad4)") (class "Default")
      (node (ref "P33") (pin "4") (pinfunction "4_4") (pintype "passive+no_connect"))
    )
    (net (code "105") (name "unconnected-(P40-Pad2)") (class "Default")
      (node (ref "P40") (pin "2") (pinfunction "2_2") (pintype "passive"))
    )
    (net (code "106") (name "unconnected-(P41-Pad2)") (class "Default")
      (node (ref "P41") (pin "2") (pinfunction "2_2") (pintype "passive"))
    )
    (net (code "107") (name "unconnected-(P42-Pad2)") (class "Default")
      (node (ref "P42") (pin "2") (pinfunction "2_2") (pintype "passive"))
    )
    (net (code "108") (name "unconnected-(P43-Pad2)") (class "Default")
      (node (ref "P43") (pin "2") (pinfunction "2_2") (pintype "passive"))
    )
    (net (code "109") (name "unconnected-(P44-Pad2)") (class "Default")
      (node (ref "P44") (pin "2") (pinfunction "2_2") (pintype "passive"))
    )
    (net (code "110") (name "unconnected-(P45-Pad2)") (class "Default")
      (node (ref "P45") (pin "2") (pinfunction "2_2") (pintype "passive"))
    )
    (net (code "111") (name "unconnected-(U3-GP0{slash}SSPND-Pad16)") (class "Default")
      (node (ref "U3") (pin "16") (pinfunction "GP0/SSPND_16") (pintype "bidirectional"))
    )
    (net (code "112") (name "unconnected-(U3-GP1{slash}USBCFG-Pad15)") (class "Default")
      (node (ref "U3") (pin "15") (pinfunction "GP1/USBCFG_15") (pintype "bidirectional"))
    )
    (net (code "113") (name "unconnected-(U3-GP2-Pad14)") (class "Default")
      (node (ref "U3") (pin "14") (pinfunction "GP2_14") (pintype "bidirectional"))
    )
    (net (code "114") (name "unconnected-(U3-GP3-Pad9)") (class "Default")
      (node (ref "U3") (pin "9") (pinfunction "GP3_9") (pintype "bidirectional"))
    )
    (net (code "115") (name "unconnected-(U3-GP4-Pad8)") (class "Default")
      (node (ref "U3") (pin "8") (pinfunction "GP4_8") (pintype "passive"))
    )
    (net (code "116") (name "unconnected-(U3-GP5-Pad7)") (class "Default")
      (node (ref "U3") (pin "7") (pinfunction "GP5_7") (pintype "passive"))
    )
    (net (code "117") (name "unconnected-(U3-~{CTS}-Pad13)") (class "Default")
      (node (ref "U3") (pin "13") (pinfunction "~{CTS}_13") (pintype "output+no_connect"))
    )
    (net (code "118") (name "unconnected-(U3-~{RTS}-Pad11)") (class "Default")
      (node (ref "U3") (pin "11") (pinfunction "~{RTS}_11") (pintype "input+no_connect"))
    )
  )
)
